# CHARGING.net
KiCad netlist of a schematic drawn in Altium Designer
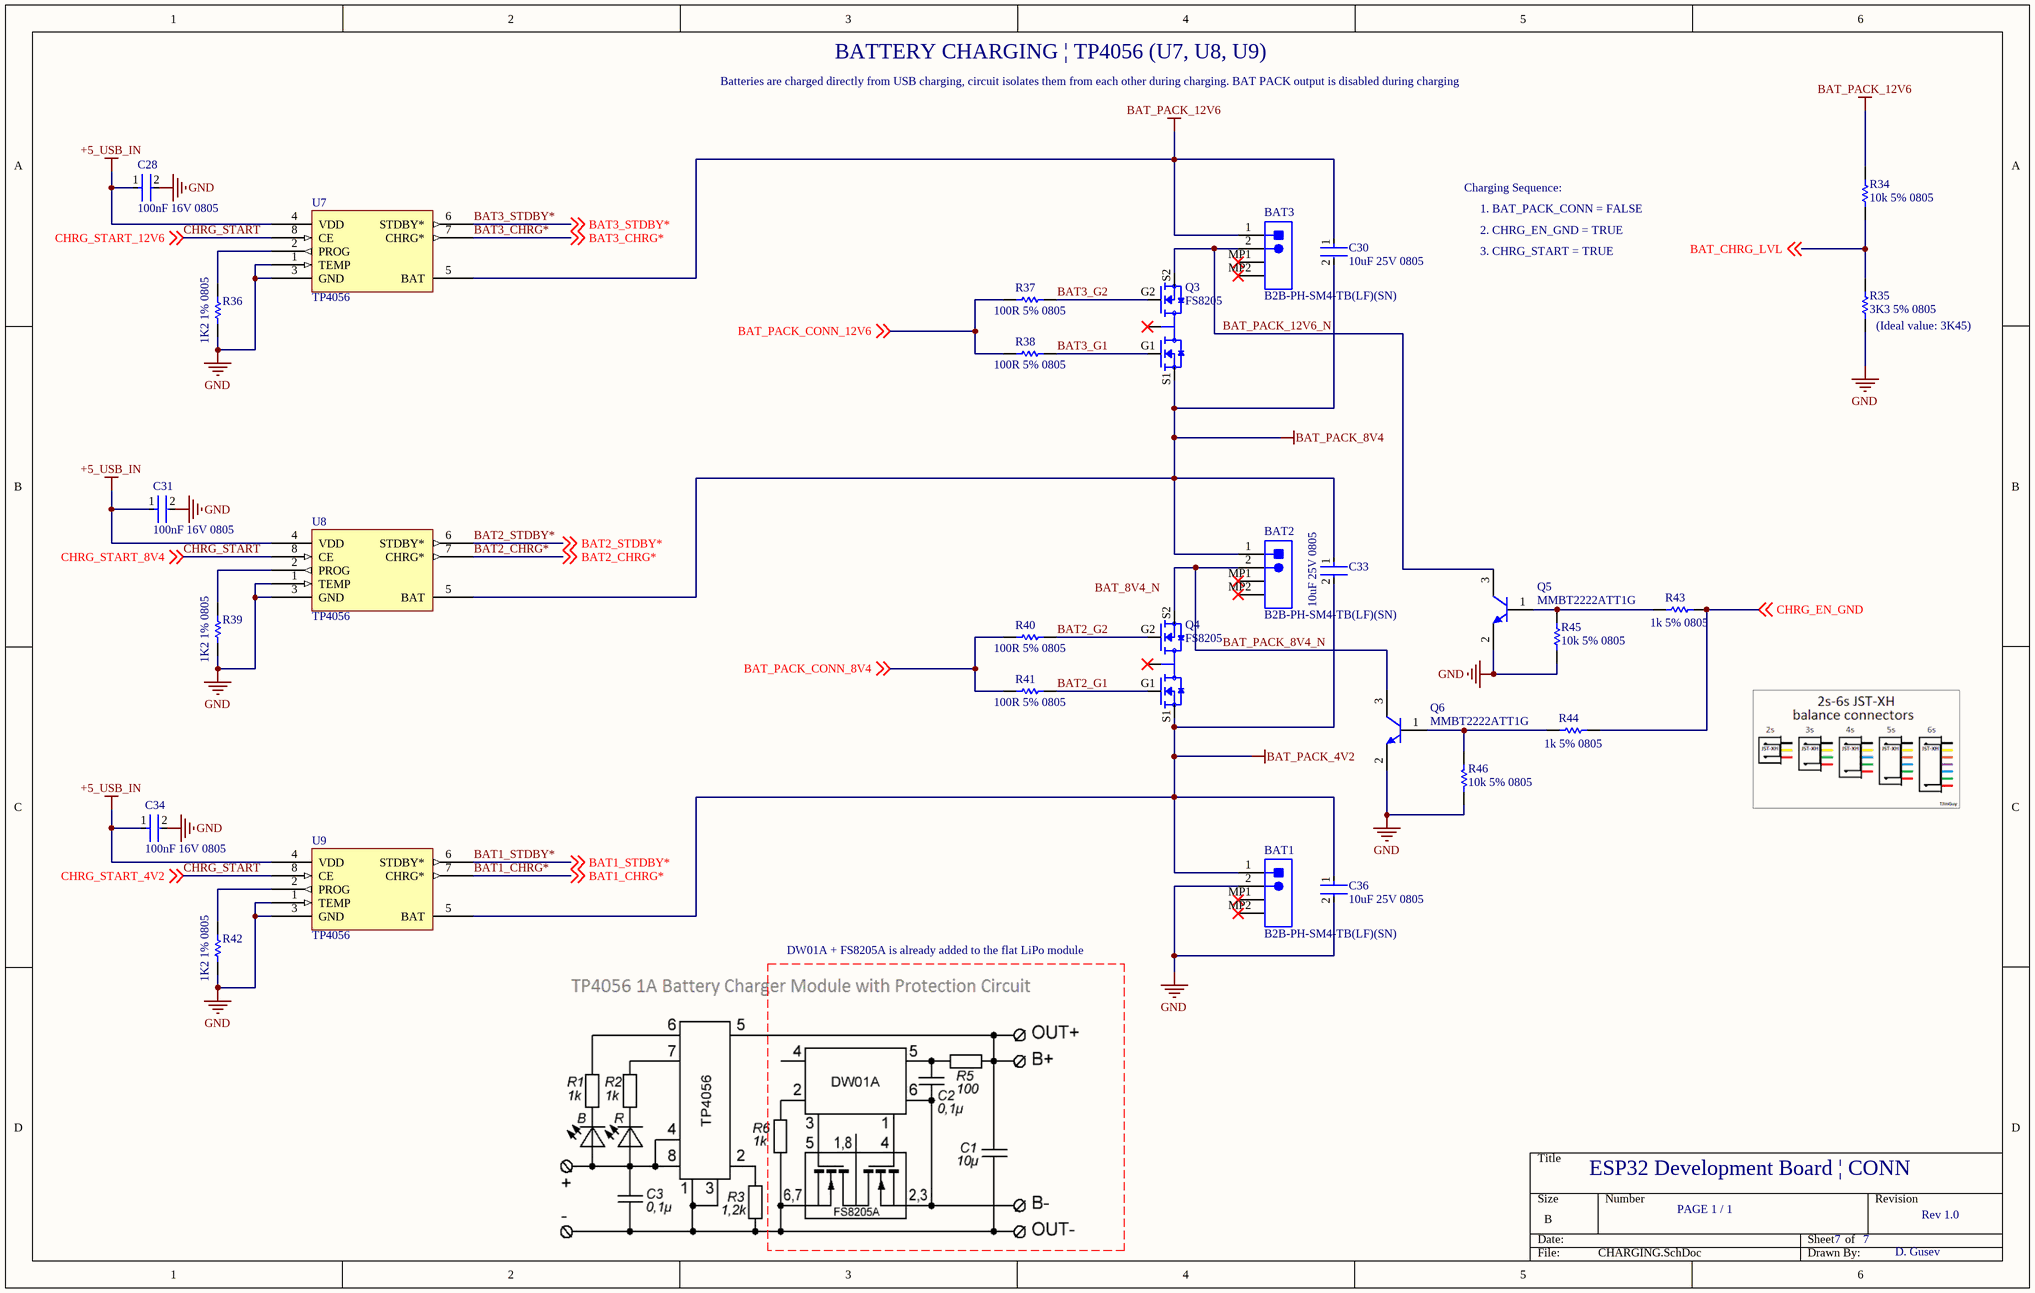
[diagram p0: CHARGING.SchDoc]

(export (version "E")
  (design (tool "Eeschema 10.0.6"))
  (components
    (comp (ref "BAT1")
      (value "B2B-PH-SM4-TB(LF)(SN)")
      (footprint "JST-B2B-PH-SM4-TB-2_V")
      (description "Male Header, Pitch 2 mm, 1 x 2 Position, Height 6.6 mm, RoHS, Tape and Reel")
      (fields (field (name "MANUFACTURER") "JST"))
      (libsource (lib "Altium Content Vault") (part "CN-1P-2M-R2"))
    )
    (comp (ref "BAT2")
      (value "B2B-PH-SM4-TB(LF)(SN)")
      (footprint "JST-B2B-PH-SM4-TB-2_V")
      (description "Male Header, Pitch 2 mm, 1 x 2 Position, Height 6.6 mm, RoHS, Tape and Reel")
      (fields (field (name "MANUFACTURER") "JST"))
      (libsource (lib "Altium Content Vault") (part "CN-1P-2M-R2"))
    )
    (comp (ref "BAT3")
      (value "B2B-PH-SM4-TB(LF)(SN)")
      (footprint "JST-B2B-PH-SM4-TB-2_V")
      (description "Male Header, Pitch 2 mm, 1 x 2 Position, Height 6.6 mm, RoHS, Tape and Reel")
      (fields (field (name "MANUFACTURER") "JST"))
      (libsource (lib "Altium Content Vault") (part "CN-1P-2M-R2"))
    )
    (comp (ref "C28")
      (value "100nF 16V 0805")
      (footprint "FP-C0805C-DN-MFG")
      (description "CAP CER 0.1UF 16V X7R 0805")
      (fields
        (field (name "OCTOPART") "https://octopart.com/c0805c104j4ractu-kemet-12563748")
        (field (name "MANUFACTURER PART NUMBER") "C0805C104J4RACTU")
      )
      (libsource (lib "Altium Content Vault") (part "b4654b650e69147ec39a6b967a45e02"))
    )
    (comp (ref "C30")
      (value "10uF 25V 0805")
      (footprint "FP-GRM21B-0_15-IPC_C")
      (description "Chip Multilayer Ceramic Capacitors for General Purpose, 0805, 10uF, X5R, 15%, 10%, 25V")
      (fields (field (name "VOLTAGE") "25V") (field (name "TOLERANCE") "10%"))
      (libsource (lib "Altium Content Vault") (part "b4654b650e69147ec39a6b967a45e02"))
    )
    (comp (ref "C31")
      (value "100nF 16V 0805")
      (footprint "FP-C0805C-DN-MFG")
      (description "CAP CER 0.1UF 16V X7R 0805")
      (fields
        (field (name "OCTOPART") "https://octopart.com/c0805c104j4ractu-kemet-12563748")
        (field (name "MANUFACTURER PART NUMBER") "C0805C104J4RACTU")
      )
      (libsource (lib "Altium Content Vault") (part "b4654b650e69147ec39a6b967a45e02"))
    )
    (comp (ref "C33")
      (value "10uF 25V 0805")
      (footprint "FP-GRM21B-0_15-IPC_C")
      (description "Chip Multilayer Ceramic Capacitors for General Purpose, 0805, 10uF, X5R, 15%, 10%, 25V")
      (fields (field (name "VOLTAGE") "25V") (field (name "TOLERANCE") "10%"))
      (libsource (lib "Altium Content Vault") (part "b4654b650e69147ec39a6b967a45e02"))
    )
    (comp (ref "C34")
      (value "100nF 16V 0805")
      (footprint "FP-C0805C-DN-MFG")
      (description "CAP CER 0.1UF 16V X7R 0805")
      (fields
        (field (name "OCTOPART") "https://octopart.com/c0805c104j4ractu-kemet-12563748")
        (field (name "MANUFACTURER PART NUMBER") "C0805C104J4RACTU")
      )
      (libsource (lib "Altium Content Vault") (part "b4654b650e69147ec39a6b967a45e02"))
    )
    (comp (ref "C36")
      (value "10uF 25V 0805")
      (footprint "FP-GRM21B-0_15-IPC_C")
      (description "Chip Multilayer Ceramic Capacitors for General Purpose, 0805, 10uF, X5R, 15%, 10%, 25V")
      (fields (field (name "VOLTAGE") "25V") (field (name "TOLERANCE") "10%"))
      (libsource (lib "Altium Content Vault") (part "b4654b650e69147ec39a6b967a45e02"))
    )
    (comp (ref "Q3")
      (value "FS8205")
      (footprint "FS8205")
      (description "Dual N-Channel Enhancement Mode Power MOSFET")
      (fields (field (name "MF") "Fortune Semiconductor"))
      (libsource (lib "ddrlegobrick") (part "FS8205"))
    )
    (comp (ref "Q4")
      (value "FS8205")
      (footprint "FS8205")
      (description "Dual N-Channel Enhancement Mode Power MOSFET")
      (fields (field (name "MF") "Fortune Semiconductor"))
      (libsource (lib "ddrlegobrick") (part "FS8205"))
    )
    (comp (ref "Q5")
      (value "MMBT2222ATT1G")
      (footprint "ONSC-SC-75-3-463-01_V")
      (description "General Purpose Transistor, NPN Silicon, 3-Pin SC-75, Pb-Free, Tape and Reel")
      (fields (field (name "MANUFACTURER") "On Semiconductor"))
      (libsource (lib "Altium Content Vault") (part "ONSC-NPN-B1E2C3-3"))
    )
    (comp (ref "Q6")
      (value "MMBT2222ATT1G")
      (footprint "ONSC-SC-75-3-463-01_V")
      (description "General Purpose Transistor, NPN Silicon, 3-Pin SC-75, Pb-Free, Tape and Reel")
      (fields (field (name "MANUFACTURER") "On Semiconductor"))
      (libsource (lib "Altium Content Vault") (part "ONSC-NPN-B1E2C3-3"))
    )
    (comp (ref "R34")
      (value "10k 5% 0805")
      (footprint "RESC2013X60X35NL10T20")
      (description "Chip Resistor, 10 KOhm, +/- 1%, 0.125 W, -55 to 155 degC, 0805 (2012 Metric), RoHS, Tape and Reel")
      (fields (field (name "MANUFACTURER") "Yageo"))
      (libsource (lib "Altium Content Vault") (part "RES-2"))
    )
    (comp (ref "R35")
      (value "3K3 5% 0805")
      (footprint "RESC2013X60X35ML10T20")
      (description "Chip Resistor, 3.3 KOhm, +/- 1%, 0.125 W, -55 to 155 degC, 0805 (2012 Metric), RoHS, Tape and Reel")
      (fields (field (name "TOLERANCE") "1%") (field (name "MANUFACTURER") "Yageo"))
      (libsource (lib "Altium Content Vault") (part "RES-2"))
    )
    (comp (ref "R36")
      (value "1K2 1% 0805")
      (footprint "RESC2013X70X40ML20T20")
      (fields (field (name "MANUFACTURER") "Panasonic") (field (name "PART NUMBER") "ERJ6ENF1201V"))
      (libsource (lib "Altium Content Vault") (part "RES"))
    )
    (comp (ref "R37")
      (value "100R 5% 0805")
      (footprint "RESC2013X60X35ML10T20")
      (description "Chip Resistor, 100 Ohm, +/-1%, 0.125 W, -55 to 155 degC, 0805 (2012 Metric), RoHS, Tape and Reel")
      (fields (field (name "TOLERANCE") "1%") (field (name "MANUFACTURER") "Yageo"))
      (libsource (lib "Altium Content Vault") (part "RES-2"))
    )
    (comp (ref "R38")
      (value "100R 5% 0805")
      (footprint "RESC2013X60X35ML10T20")
      (description "Chip Resistor, 100 Ohm, +/-1%, 0.125 W, -55 to 155 degC, 0805 (2012 Metric), RoHS, Tape and Reel")
      (fields (field (name "TOLERANCE") "1%") (field (name "MANUFACTURER") "Yageo"))
      (libsource (lib "Altium Content Vault") (part "RES-2"))
    )
    (comp (ref "R39")
      (value "1K2 1% 0805")
      (footprint "RESC2013X70X40ML20T20")
      (fields (field (name "MANUFACTURER") "Panasonic") (field (name "PART NUMBER") "ERJ6ENF1201V"))
      (libsource (lib "Altium Content Vault") (part "RES"))
    )
    (comp (ref "R40")
      (value "100R 5% 0805")
      (footprint "RESC2013X60X35ML10T20")
      (description "Chip Resistor, 100 Ohm, +/-1%, 0.125 W, -55 to 155 degC, 0805 (2012 Metric), RoHS, Tape and Reel")
      (fields (field (name "TOLERANCE") "1%") (field (name "MANUFACTURER") "Yageo"))
      (libsource (lib "Altium Content Vault") (part "RES-2"))
    )
    (comp (ref "R41")
      (value "100R 5% 0805")
      (footprint "RESC2013X60X35ML10T20")
      (description "Chip Resistor, 100 Ohm, +/-1%, 0.125 W, -55 to 155 degC, 0805 (2012 Metric), RoHS, Tape and Reel")
      (fields (field (name "TOLERANCE") "1%") (field (name "MANUFACTURER") "Yageo"))
      (libsource (lib "Altium Content Vault") (part "RES-2"))
    )
    (comp (ref "R42")
      (value "1K2 1% 0805")
      (footprint "RESC2013X70X40ML20T20")
      (fields (field (name "MANUFACTURER") "Panasonic") (field (name "PART NUMBER") "ERJ6ENF1201V"))
      (libsource (lib "Altium Content Vault") (part "RES"))
    )
    (comp (ref "R43")
      (value "1k 5% 0805")
      (footprint "RESC2013X60X35ML10T20")
      (description "Chip Resistor, 1 KOhm, +/- 1%, 125 mW, -55 to 155 degC, 0805 (2012 Metric), RoHS, Tape and Reel")
      (fields (field (name "TOLERANCE") "1%") (field (name "MANUFACTURER") "Yageo"))
      (libsource (lib "Altium Content Vault") (part "RES-2"))
    )
    (comp (ref "R44")
      (value "1k 5% 0805")
      (footprint "RESC2013X60X35ML10T20")
      (description "Chip Resistor, 1 KOhm, +/- 1%, 125 mW, -55 to 155 degC, 0805 (2012 Metric), RoHS, Tape and Reel")
      (fields (field (name "TOLERANCE") "1%") (field (name "MANUFACTURER") "Yageo"))
      (libsource (lib "Altium Content Vault") (part "RES-2"))
    )
    (comp (ref "R45")
      (value "10k 5% 0805")
      (footprint "RESC2013X60X35NL10T20")
      (description "Chip Resistor, 10 KOhm, +/- 1%, 0.125 W, -55 to 155 degC, 0805 (2012 Metric), RoHS, Tape and Reel")
      (fields (field (name "MANUFACTURER") "Yageo"))
      (libsource (lib "Altium Content Vault") (part "RES-2"))
    )
    (comp (ref "R46")
      (value "10k 5% 0805")
      (footprint "RESC2013X60X35NL10T20")
      (description "Chip Resistor, 10 KOhm, +/- 1%, 0.125 W, -55 to 155 degC, 0805 (2012 Metric), RoHS, Tape and Reel")
      (fields (field (name "MANUFACTURER") "Yageo"))
      (libsource (lib "Altium Content Vault") (part "RES-2"))
    )
    (comp (ref "U7")
      (value "TP4056")
      (footprint "TP4056")
      (description "1-CELL LI+ BATTERY CHARGER")
      (libsource (lib "ddrlegobrick") (part "TP4056"))
    )
    (comp (ref "U8")
      (value "TP4056")
      (footprint "TP4056")
      (description "1-CELL LI+ BATTERY CHARGER")
      (libsource (lib "ddrlegobrick") (part "TP4056"))
    )
    (comp (ref "U9")
      (value "TP4056")
      (footprint "TP4056")
      (description "1-CELL LI+ BATTERY CHARGER")
      (libsource (lib "ddrlegobrick") (part "TP4056"))
    )
  )
  (nets
    (net (code "1") (name "+5_USB_IN") (class "Default")
      (node (ref "C28") (pin "1") (pinfunction "1_1") (pintype "passive"))
      (node (ref "C31") (pin "1") (pinfunction "1_1") (pintype "passive"))
      (node (ref "C34") (pin "1") (pinfunction "1_1") (pintype "passive"))
      (node (ref "U7") (pin "4") (pinfunction "VDD_4") (pintype "power_in"))
      (node (ref "U8") (pin "4") (pinfunction "VDD_4") (pintype "power_in"))
      (node (ref "U9") (pin "4") (pinfunction "VDD_4") (pintype "power_in"))
    )
    (net (code "2") (name "/BAT2_G1") (class "Default")
      (node (ref "Q4") (pin "G1") (pinfunction "G1_G1") (pintype "passive"))
      (node (ref "R41") (pin "2") (pinfunction "2_2") (pintype "passive"))
    )
    (net (code "3") (name "/BAT2_G2") (class "Default")
      (node (ref "Q4") (pin "G2") (pinfunction "G2_G2") (pintype "passive"))
      (node (ref "R40") (pin "2") (pinfunction "2_2") (pintype "passive"))
    )
    (net (code "4") (name "/BAT3_G1") (class "Default")
      (node (ref "Q3") (pin "G1") (pinfunction "G1_G1") (pintype "passive"))
      (node (ref "R38") (pin "2") (pinfunction "2_2") (pintype "passive"))
    )
    (net (code "5") (name "/BAT3_G2") (class "Default")
      (node (ref "Q3") (pin "G2") (pinfunction "G2_G2") (pintype "passive"))
      (node (ref "R37") (pin "2") (pinfunction "2_2") (pintype "passive"))
    )
    (net (code "7") (name "/BAT_PACK_8V4_N") (class "Default")
      (node (ref "BAT2") (pin "2") (pinfunction "2_2") (pintype "passive"))
      (node (ref "Q4") (pin "S2") (pinfunction "S2_S2") (pintype "passive"))
      (node (ref "Q6") (pin "3") (pinfunction "C_3") (pintype "passive"))
    )
    (net (code "8") (name "/BAT_PACK_12V6_N") (class "Default")
      (node (ref "BAT3") (pin "2") (pinfunction "2_2") (pintype "passive"))
      (node (ref "Q3") (pin "S2") (pinfunction "S2_S2") (pintype "passive"))
      (node (ref "Q5") (pin "3") (pinfunction "C_3") (pintype "passive"))
    )
    (net (code "9") (name "BAT1_CHRG*") (class "Default")
      (node (ref "U9") (pin "7") (pinfunction "CHRG*_7") (pintype "output"))
    )
    (net (code "10") (name "BAT1_STDBY*") (class "Default")
      (node (ref "U9") (pin "6") (pinfunction "STDBY*_6") (pintype "output"))
    )
    (net (code "11") (name "BAT2_CHRG*") (class "Default")
      (node (ref "U8") (pin "7") (pinfunction "CHRG*_7") (pintype "output"))
    )
    (net (code "12") (name "BAT2_STDBY*") (class "Default")
      (node (ref "U8") (pin "6") (pinfunction "STDBY*_6") (pintype "output"))
    )
    (net (code "13") (name "BAT3_CHRG*") (class "Default")
      (node (ref "U7") (pin "7") (pinfunction "CHRG*_7") (pintype "output"))
    )
    (net (code "14") (name "BAT3_STDBY*") (class "Default")
      (node (ref "U7") (pin "6") (pinfunction "STDBY*_6") (pintype "output"))
    )
    (net (code "15") (name "BAT_CHRG_LVL") (class "Default")
      (node (ref "R34") (pin "1") (pinfunction "1_1") (pintype "passive"))
      (node (ref "R35") (pin "2") (pinfunction "2_2") (pintype "passive"))
    )
    (net (code "16") (name "BAT_PACK_4V2") (class "Default")
      (node (ref "BAT1") (pin "1") (pinfunction "1_1") (pintype "passive"))
      (node (ref "C33") (pin "2") (pinfunction "2_2") (pintype "passive"))
      (node (ref "C36") (pin "1") (pinfunction "1_1") (pintype "passive"))
      (node (ref "Q4") (pin "S1") (pinfunction "S1_S1") (pintype "passive"))
      (node (ref "U9") (pin "5") (pinfunction "BAT_5") (pintype "power_in"))
    )
    (net (code "17") (name "BAT_PACK_8V4") (class "Default")
      (node (ref "BAT2") (pin "1") (pinfunction "1_1") (pintype "passive"))
      (node (ref "C30") (pin "2") (pinfunction "2_2") (pintype "passive"))
      (node (ref "C33") (pin "1") (pinfunction "1_1") (pintype "passive"))
      (node (ref "Q3") (pin "S1") (pinfunction "S1_S1") (pintype "passive"))
      (node (ref "U8") (pin "5") (pinfunction "BAT_5") (pintype "power_in"))
    )
    (net (code "18") (name "BAT_PACK_12V6") (class "Default")
      (node (ref "BAT3") (pin "1") (pinfunction "1_1") (pintype "passive"))
      (node (ref "C30") (pin "1") (pinfunction "1_1") (pintype "passive"))
      (node (ref "R34") (pin "2") (pinfunction "2_2") (pintype "passive"))
      (node (ref "U7") (pin "5") (pinfunction "BAT_5") (pintype "power_in"))
    )
    (net (code "19") (name "BAT_PACK_CONN_8V4") (class "Default")
      (node (ref "R40") (pin "1") (pinfunction "1_1") (pintype "passive"))
      (node (ref "R41") (pin "1") (pinfunction "1_1") (pintype "passive"))
    )
    (net (code "20") (name "BAT_PACK_CONN_12V6") (class "Default")
      (node (ref "R37") (pin "1") (pinfunction "1_1") (pintype "passive"))
      (node (ref "R38") (pin "1") (pinfunction "1_1") (pintype "passive"))
    )
    (net (code "21") (name "CHRG_EN_GND") (class "Default")
      (node (ref "R43") (pin "2") (pinfunction "2_2") (pintype "passive"))
      (node (ref "R44") (pin "2") (pinfunction "2_2") (pintype "passive"))
    )
    (net (code "22") (name "CHRG_START_12V6") (class "Default")
      (node (ref "U7") (pin "8") (pinfunction "CE_8") (pintype "input"))
      (node (ref "U8") (pin "8") (pinfunction "CE_8") (pintype "input"))
      (node (ref "U9") (pin "8") (pinfunction "CE_8") (pintype "input"))
    )
    (net (code "23") (name "GND") (class "Default")
      (node (ref "BAT1") (pin "2") (pinfunction "2_2") (pintype "passive"))
      (node (ref "C28") (pin "2") (pinfunction "2_2") (pintype "passive"))
      (node (ref "C31") (pin "2") (pinfunction "2_2") (pintype "passive"))
      (node (ref "C34") (pin "2") (pinfunction "2_2") (pintype "passive"))
      (node (ref "C36") (pin "2") (pinfunction "2_2") (pintype "passive"))
      (node (ref "Q5") (pin "2") (pinfunction "E_2") (pintype "passive"))
      (node (ref "Q6") (pin "2") (pinfunction "E_2") (pintype "passive"))
      (node (ref "R35") (pin "1") (pinfunction "1_1") (pintype "passive"))
      (node (ref "R36") (pin "1") (pinfunction "1_1") (pintype "passive"))
      (node (ref "R39") (pin "1") (pinfunction "1_1") (pintype "passive"))
      (node (ref "R42") (pin "1") (pinfunction "1_1") (pintype "passive"))
      (node (ref "R45") (pin "1") (pinfunction "1_1") (pintype "passive"))
      (node (ref "R46") (pin "2") (pinfunction "2_2") (pintype "passive"))
      (node (ref "U7") (pin "1") (pinfunction "TEMP_1") (pintype "input"))
      (node (ref "U7") (pin "3") (pinfunction "GND_3") (pintype "passive"))
      (node (ref "U8") (pin "1") (pinfunction "TEMP_1") (pintype "input"))
      (node (ref "U8") (pin "3") (pinfunction "GND_3") (pintype "passive"))
      (node (ref "U9") (pin "1") (pinfunction "TEMP_1") (pintype "input"))
      (node (ref "U9") (pin "3") (pinfunction "GND_3") (pintype "passive"))
    )
    (net (code "24") (name "Net-(Q5-B)") (class "Default")
      (node (ref "Q5") (pin "1") (pinfunction "B_1") (pintype "passive"))
      (node (ref "R43") (pin "1") (pinfunction "1_1") (pintype "passive"))
      (node (ref "R45") (pin "2") (pinfunction "2_2") (pintype "passive"))
    )
    (net (code "25") (name "Net-(Q6-B)") (class "Default")
      (node (ref "Q6") (pin "1") (pinfunction "B_1") (pintype "passive"))
      (node (ref "R44") (pin "1") (pinfunction "1_1") (pintype "passive"))
      (node (ref "R46") (pin "1") (pinfunction "1_1") (pintype "passive"))
    )
    (net (code "26") (name "Net-(U7-PROG)") (class "Default")
      (node (ref "R36") (pin "2") (pinfunction "2_2") (pintype "passive"))
      (node (ref "U7") (pin "2") (pinfunction "PROG_2") (pintype "output"))
    )
    (net (code "27") (name "Net-(U8-PROG)") (class "Default")
      (node (ref "R39") (pin "2") (pinfunction "2_2") (pintype "passive"))
      (node (ref "U8") (pin "2") (pinfunction "PROG_2") (pintype "output"))
    )
    (net (code "28") (name "Net-(U9-PROG)") (class "Default")
      (node (ref "R42") (pin "2") (pinfunction "2_2") (pintype "passive"))
      (node (ref "U9") (pin "2") (pinfunction "PROG_2") (pintype "output"))
    )
    (net (code "29") (name "unconnected-(BAT1-PadMP1)") (class "Default")
      (node (ref "BAT1") (pin "MP1") (pinfunction "MP1_MP1") (pintype "passive+no_connect"))
    )
    (net (code "30") (name "unconnected-(BAT1-PadMP2)") (class "Default")
      (node (ref "BAT1") (pin "MP2") (pinfunction "MP2_MP2") (pintype "passive+no_connect"))
    )
    (net (code "31") (name "unconnected-(BAT2-PadMP1)") (class "Default")
      (node (ref "BAT2") (pin "MP1") (pinfunction "MP1_MP1") (pintype "passive+no_connect"))
    )
    (net (code "32") (name "unconnected-(BAT2-PadMP2)") (class "Default")
      (node (ref "BAT2") (pin "MP2") (pinfunction "MP2_MP2") (pintype "passive+no_connect"))
    )
    (net (code "33") (name "unconnected-(BAT3-PadMP1)") (class "Default")
      (node (ref "BAT3") (pin "MP1") (pinfunction "MP1_MP1") (pintype "passive+no_connect"))
    )
    (net (code "34") (name "unconnected-(BAT3-PadMP2)") (class "Default")
      (node (ref "BAT3") (pin "MP2") (pinfunction "MP2_MP2") (pintype "passive+no_connect"))
    )
    (net (code "35") (name "unconnected-(Q3-PadD12)") (class "Default")
      (node (ref "Q3") (pin "D12") (pinfunction "D12_D12") (pintype "passive+no_connect"))
    )
    (net (code "36") (name "unconnected-(Q4-PadD12)") (class "Default")
      (node (ref "Q4") (pin "D12") (pinfunction "D12_D12") (pintype "passive+no_connect"))
    )
  )
)
